# connectors_drivers.net
KiCad netlist of a schematic drawn in Altium Designer
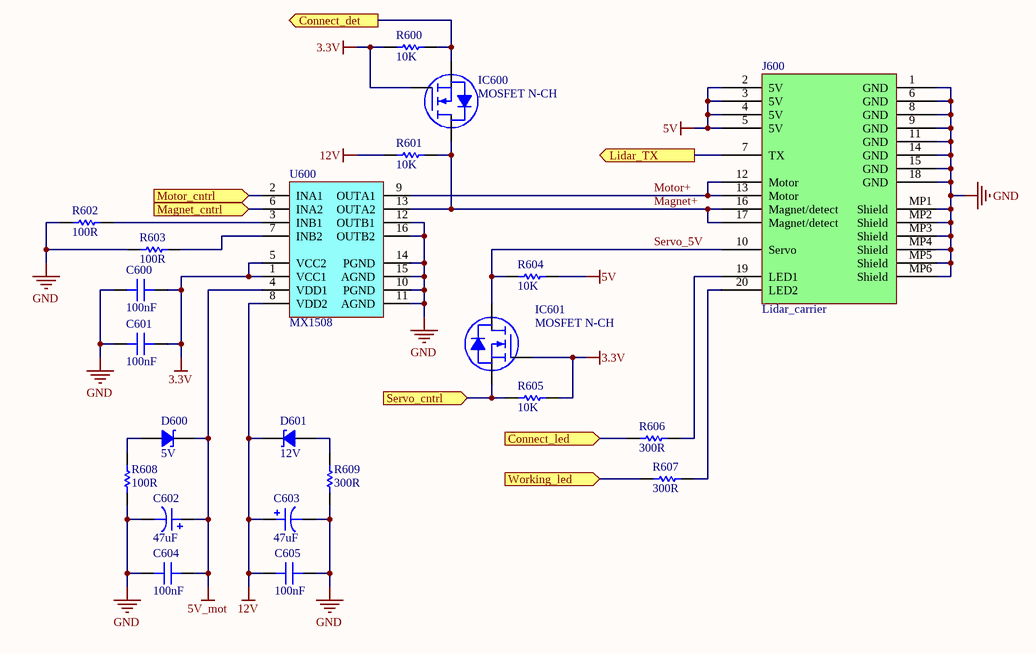
[diagram p0: connectors&drivers.SchDoc]

(export (version "E")
  (design (tool "Eeschema 10.0.6"))
  (components
    (comp (ref "C600")
      (value "100nF")
      (footprint "CAP 0603")
      (description "SMT Capacitor")
      (libsource (lib "Schlib1") (part "Capacitor"))
    )
    (comp (ref "C601")
      (value "100nF")
      (footprint "CAP 0603")
      (description "SMT Capacitor")
      (libsource (lib "Schlib1") (part "Capacitor"))
    )
    (comp (ref "C602")
      (value "47uF")
      (footprint "CAP ALSMD ELEC 6.6MM H5.7MM")
      (description "SMT Polarised Capacitor")
      (libsource (lib "Schlib1") (part "Capacitor polarized"))
    )
    (comp (ref "C603")
      (value "47uF")
      (footprint "CAP ALSMD ELEC 6.6MM H5.7MM")
      (description "SMT Polarised Capacitor")
      (libsource (lib "Schlib1") (part "Capacitor polarized"))
    )
    (comp (ref "C604")
      (value "100nF")
      (footprint "CAP 0603")
      (description "SMT Capacitor")
      (libsource (lib "Schlib1") (part "Capacitor"))
    )
    (comp (ref "C605")
      (value "100nF")
      (footprint "CAP 0603")
      (description "SMT Capacitor")
      (libsource (lib "Schlib1") (part "Capacitor"))
    )
    (comp (ref "D600")
      (value "5V")
      (footprint "Bourns DO214AC SMA")
      (description "Zener Diode")
      (libsource (lib "Schlib1") (part "Diode Zener"))
    )
    (comp (ref "D601")
      (value "12V")
      (footprint "Bourns DO214AC SMA")
      (description "Zener Diode")
      (libsource (lib "Schlib1") (part "Diode Zener"))
    )
    (comp (ref "IC600")
      (value "MOSFET N-CH")
      (footprint "SOT-23")
      (libsource (lib "Schlib1") (part "MOSFET N-CH"))
    )
    (comp (ref "IC601")
      (value "MOSFET N-CH")
      (footprint "SOT-23")
      (libsource (lib "Schlib1") (part "MOSFET N-CH"))
    )
    (comp (ref "J600")
      (value "Lidar_carrier")
      (footprint "2167010209")
      (libsource (lib "Schlib1") (part "Lidar_carrier"))
    )
    (comp (ref "R600")
      (value "10K")
      (footprint "RES 0603")
      (description "Resistor")
      (fields (field (name "PUBLISHER") "Altium Limited"))
      (libsource (lib "Schlib1") (part "Res"))
    )
    (comp (ref "R601")
      (value "10K")
      (footprint "RES 0603")
      (description "Resistor")
      (fields (field (name "PUBLISHER") "Altium Limited"))
      (libsource (lib "Schlib1") (part "Res"))
    )
    (comp (ref "R602")
      (value "100R")
      (footprint "RES 0603")
      (description "Resistor")
      (fields (field (name "PUBLISHER") "Altium Limited"))
      (libsource (lib "Schlib1") (part "Res"))
    )
    (comp (ref "R603")
      (value "100R")
      (footprint "RES 0603")
      (description "Resistor")
      (fields (field (name "PUBLISHER") "Altium Limited"))
      (libsource (lib "Schlib1") (part "Res"))
    )
    (comp (ref "R604")
      (value "10K")
      (footprint "RES 0603")
      (description "Resistor")
      (fields (field (name "PUBLISHER") "Altium Limited"))
      (libsource (lib "Schlib1") (part "Res"))
    )
    (comp (ref "R605")
      (value "10K")
      (footprint "RES 0603")
      (description "Resistor")
      (fields (field (name "PUBLISHER") "Altium Limited"))
      (libsource (lib "Schlib1") (part "Res"))
    )
    (comp (ref "R606")
      (value "300R")
      (footprint "RES 0603")
      (description "Resistor")
      (fields (field (name "PUBLISHER") "Altium Limited"))
      (libsource (lib "Schlib1") (part "Res"))
    )
    (comp (ref "R607")
      (value "300R")
      (footprint "RES 0603")
      (description "Resistor")
      (fields (field (name "PUBLISHER") "Altium Limited"))
      (libsource (lib "Schlib1") (part "Res"))
    )
    (comp (ref "R608")
      (value "100R")
      (footprint "RES 1206")
      (description "Resistor")
      (fields (field (name "PUBLISHER") "Altium Limited"))
      (libsource (lib "Schlib1") (part "Res"))
    )
    (comp (ref "R609")
      (value "300R")
      (footprint "RES 1206")
      (description "Resistor")
      (fields (field (name "PUBLISHER") "Altium Limited"))
      (libsource (lib "Schlib1") (part "Res"))
    )
    (comp (ref "U600") (value "MX1508") (footprint "TI SOP-16 D") (libsource (lib "Schlib1") (part "MX1508")))
  )
  (nets
    (net (code "1") (name "/Connect_det") (class "Default")
      (node (ref "IC600") (pin "2") (pinfunction "S_2") (pintype "passive"))
      (node (ref "R600") (pin "1") (pinfunction "1_1") (pintype "passive"))
    )
    (net (code "2") (name "/Connect_led") (class "Default")
      (node (ref "R606") (pin "2") (pinfunction "2_2") (pintype "passive"))
    )
    (net (code "3") (name "/Lidar_TX") (class "Default")
      (node (ref "J600") (pin "7") (pinfunction "TX_7") (pintype "passive"))
    )
    (net (code "4") (name "/Magnet+") (class "Default")
      (node (ref "IC600") (pin "3") (pinfunction "D_3") (pintype "passive"))
      (node (ref "J600") (pin "16") (pinfunction "Magnet/detect_16") (pintype "passive"))
      (node (ref "J600") (pin "17") (pinfunction "Magnet/detect_17") (pintype "passive"))
      (node (ref "R601") (pin "1") (pinfunction "1_1") (pintype "passive"))
      (node (ref "U600") (pin "13") (pinfunction "OUTA2_13") (pintype "passive"))
    )
    (net (code "5") (name "/Magnet_cntrl") (class "Default")
      (node (ref "U600") (pin "6") (pinfunction "INA2_6") (pintype "passive"))
    )
    (net (code "6") (name "/Motor+") (class "Default")
      (node (ref "J600") (pin "12") (pinfunction "Motor_12") (pintype "passive"))
      (node (ref "J600") (pin "13") (pinfunction "Motor_13") (pintype "passive"))
      (node (ref "U600") (pin "9") (pinfunction "OUTA1_9") (pintype "passive"))
    )
    (net (code "7") (name "/Motor_cntrl") (class "Default")
      (node (ref "U600") (pin "2") (pinfunction "INA1_2") (pintype "passive"))
    )
    (net (code "8") (name "/Servo_5V") (class "Default")
      (node (ref "IC601") (pin "3") (pinfunction "D_3") (pintype "passive"))
      (node (ref "J600") (pin "10") (pinfunction "Servo_10") (pintype "passive"))
      (node (ref "R604") (pin "2") (pinfunction "2_2") (pintype "passive"))
    )
    (net (code "9") (name "/Servo_cntrl") (class "Default")
      (node (ref "IC601") (pin "2") (pinfunction "S_2") (pintype "passive"))
      (node (ref "R605") (pin "2") (pinfunction "2_2") (pintype "passive"))
    )
    (net (code "10") (name "/Working_led") (class "Default")
      (node (ref "R607") (pin "2") (pinfunction "2_2") (pintype "passive"))
    )
    (net (code "11") (name "3.3V") (class "Default")
      (node (ref "C600") (pin "2") (pinfunction "2_2") (pintype "passive"))
      (node (ref "C601") (pin "2") (pinfunction "2_2") (pintype "passive"))
      (node (ref "IC600") (pin "1") (pinfunction "G_1") (pintype "passive"))
      (node (ref "IC601") (pin "1") (pinfunction "G_1") (pintype "passive"))
      (node (ref "R600") (pin "2") (pinfunction "2_2") (pintype "passive"))
      (node (ref "R605") (pin "1") (pinfunction "1_1") (pintype "passive"))
      (node (ref "U600") (pin "1") (pinfunction "VCC1_1") (pintype "passive"))
      (node (ref "U600") (pin "5") (pinfunction "VCC2_5") (pintype "passive"))
    )
    (net (code "12") (name "5V") (class "Default")
      (node (ref "J600") (pin "2") (pinfunction "5V_2") (pintype "passive"))
      (node (ref "J600") (pin "3") (pinfunction "5V_3") (pintype "passive"))
      (node (ref "J600") (pin "4") (pinfunction "5V_4") (pintype "passive"))
      (node (ref "J600") (pin "5") (pinfunction "5V_5") (pintype "passive"))
      (node (ref "R604") (pin "1") (pinfunction "1_1") (pintype "passive"))
    )
    (net (code "13") (name "5V_mot") (class "Default")
      (node (ref "C602") (pin "2") (pinfunction "2_2") (pintype "passive"))
      (node (ref "C604") (pin "2") (pinfunction "2_2") (pintype "passive"))
      (node (ref "D600") (pin "2") (pinfunction "2_2") (pintype "passive"))
      (node (ref "U600") (pin "4") (pinfunction "VDD1_4") (pintype "passive"))
    )
    (net (code "14") (name "12V") (class "Default")
      (node (ref "C603") (pin "2") (pinfunction "2_2") (pintype "passive"))
      (node (ref "C605") (pin "1") (pinfunction "1_1") (pintype "passive"))
      (node (ref "D601") (pin "2") (pinfunction "2_2") (pintype "passive"))
      (node (ref "R601") (pin "2") (pinfunction "2_2") (pintype "passive"))
      (node (ref "U600") (pin "8") (pinfunction "VDD2_8") (pintype "passive"))
    )
    (net (code "15") (name "GND") (class "Default")
      (node (ref "C600") (pin "1") (pinfunction "1_1") (pintype "passive"))
      (node (ref "C601") (pin "1") (pinfunction "1_1") (pintype "passive"))
      (node (ref "C602") (pin "1") (pinfunction "1_1") (pintype "passive"))
      (node (ref "C603") (pin "1") (pinfunction "1_1") (pintype "passive"))
      (node (ref "C604") (pin "1") (pinfunction "1_1") (pintype "passive"))
      (node (ref "C605") (pin "2") (pinfunction "2_2") (pintype "passive"))
      (node (ref "J600") (pin "1") (pinfunction "GND_1") (pintype "passive"))
      (node (ref "J600") (pin "11") (pinfunction "GND_11") (pintype "passive"))
      (node (ref "J600") (pin "14") (pinfunction "GND_14") (pintype "passive"))
      (node (ref "J600") (pin "15") (pinfunction "GND_15") (pintype "passive"))
      (node (ref "J600") (pin "18") (pinfunction "GND_18") (pintype "passive"))
      (node (ref "J600") (pin "6") (pinfunction "GND_6") (pintype "passive"))
      (node (ref "J600") (pin "8") (pinfunction "GND_8") (pintype "passive"))
      (node (ref "J600") (pin "9") (pinfunction "GND_9") (pintype "passive"))
      (node (ref "J600") (pin "MP1") (pinfunction "Shield_MP1") (pintype "passive"))
      (node (ref "J600") (pin "MP2") (pinfunction "Shield_MP2") (pintype "passive"))
      (node (ref "J600") (pin "MP3") (pinfunction "Shield_MP3") (pintype "passive"))
      (node (ref "J600") (pin "MP4") (pinfunction "Shield_MP4") (pintype "passive"))
      (node (ref "J600") (pin "MP5") (pinfunction "Shield_MP5") (pintype "passive"))
      (node (ref "J600") (pin "MP6") (pinfunction "Shield_MP6") (pintype "passive"))
      (node (ref "R602") (pin "1") (pinfunction "1_1") (pintype "passive"))
      (node (ref "R603") (pin "1") (pinfunction "1_1") (pintype "passive"))
      (node (ref "R608") (pin "1") (pinfunction "1_1") (pintype "passive"))
      (node (ref "R609") (pin "1") (pinfunction "1_1") (pintype "passive"))
      (node (ref "U600") (pin "10") (pinfunction "PGND_10") (pintype "passive"))
      (node (ref "U600") (pin "11") (pinfunction "AGND_11") (pintype "passive"))
      (node (ref "U600") (pin "12") (pinfunction "OUTB1_12") (pintype "passive"))
      (node (ref "U600") (pin "14") (pinfunction "PGND_14") (pintype "passive"))
      (node (ref "U600") (pin "15") (pinfunction "AGND_15") (pintype "passive"))
      (node (ref "U600") (pin "16") (pinfunction "OUTB2_16") (pintype "passive"))
    )
    (net (code "16") (name "Net-(D600-Pad1)") (class "Default")
      (node (ref "D600") (pin "1") (pinfunction "1_1") (pintype "passive"))
      (node (ref "R608") (pin "2") (pinfunction "2_2") (pintype "passive"))
    )
    (net (code "17") (name "Net-(D601-Pad1)") (class "Default")
      (node (ref "D601") (pin "1") (pinfunction "1_1") (pintype "passive"))
      (node (ref "R609") (pin "2") (pinfunction "2_2") (pintype "passive"))
    )
    (net (code "18") (name "Net-(J600-LED1)") (class "Default")
      (node (ref "J600") (pin "19") (pinfunction "LED1_19") (pintype "passive"))
      (node (ref "R606") (pin "1") (pinfunction "1_1") (pintype "passive"))
    )
    (net (code "19") (name "Net-(J600-LED2)") (class "Default")
      (node (ref "J600") (pin "20") (pinfunction "LED2_20") (pintype "passive"))
      (node (ref "R607") (pin "1") (pinfunction "1_1") (pintype "passive"))
    )
    (net (code "20") (name "Net-(U600-INB1)") (class "Default")
      (node (ref "R602") (pin "2") (pinfunction "2_2") (pintype "passive"))
      (node (ref "U600") (pin "3") (pinfunction "INB1_3") (pintype "passive"))
    )
    (net (code "21") (name "Net-(U600-INB2)") (class "Default")
      (node (ref "R603") (pin "2") (pinfunction "2_2") (pintype "passive"))
      (node (ref "U600") (pin "7") (pinfunction "INB2_7") (pintype "passive"))
    )
  )
)
